# STM.net
KiCad netlist of a schematic drawn in Altium Designer
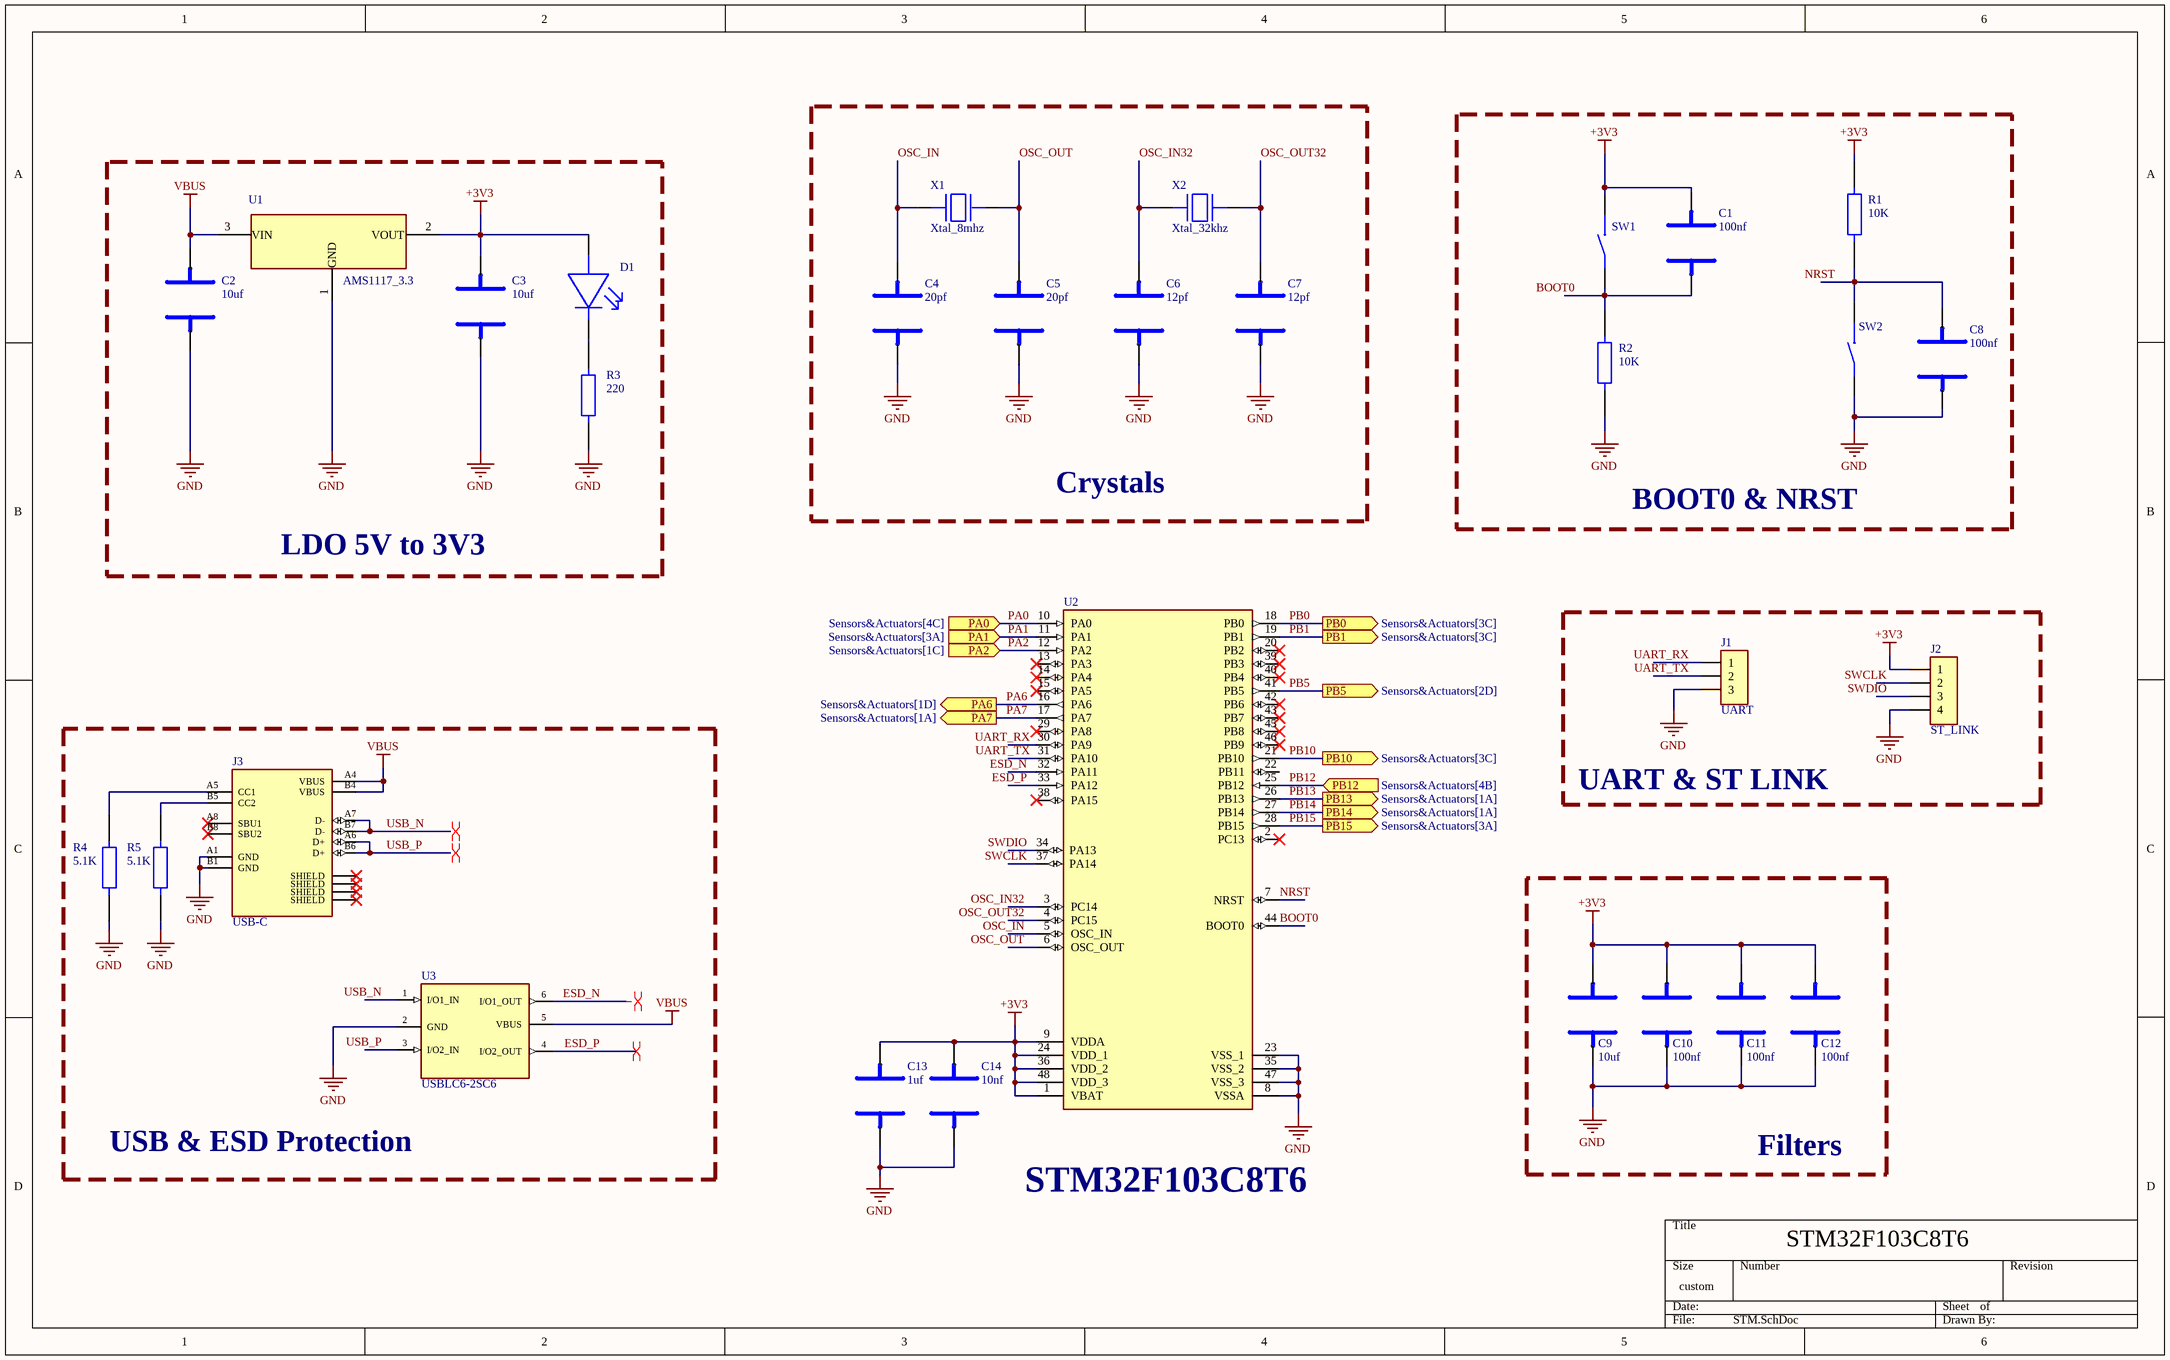
[diagram p0: STM.SchDoc]

(export (version "E")
  (design (tool "Eeschema 10.0.6"))
  (components
    (comp (ref "C1")
      (value "100nf")
      (footprint "Cap_0805")
      (description "CAP CER 100nF 50V X7R 0805")
      (fields (field (name "MFR") "Samsung Electro-Mechanics") (field (name "MFR PART#") "CL21B104KBCNNNC"))
      (libsource (lib "project") (part "Cap_0805_100nf"))
    )
    (comp (ref "C2")
      (value "10uf")
      (footprint "Cap_0805")
      (description "CAP CER 10uF 25V X5R 0805")
      (fields (field (name "MFR") "Samsung Electro-Mechanics") (field (name "MFR PART#") "CL21A106KAYNNNE"))
      (libsource (lib "project") (part "Cap_0805_10uf"))
    )
    (comp (ref "C3")
      (value "10uf")
      (footprint "Cap_0805")
      (description "CAP CER 10uF 25V X5R 0805")
      (fields (field (name "MFR") "Samsung Electro-Mechanics") (field (name "MFR PART#") "CL21A106KAYNNNE"))
      (libsource (lib "project") (part "Cap_0805_10uf"))
    )
    (comp (ref "C4")
      (value "20pf")
      (footprint "Cap_0805")
      (description "CAP CER 20pF 50V C0G 0805")
      (fields (field (name "MFR") "Samsung Electro-Mechanics") (field (name "MFR PART#") "CL21C200JBANNNC"))
      (libsource (lib "project") (part "Cap_0805_20pf"))
    )
    (comp (ref "C5")
      (value "20pf")
      (footprint "Cap_0805")
      (description "CAP CER 20pF 50V C0G 0805")
      (fields (field (name "MFR") "Samsung Electro-Mechanics") (field (name "MFR PART#") "CL21C200JBANNNC"))
      (libsource (lib "project") (part "Cap_0805_20pf"))
    )
    (comp (ref "C6")
      (value "12pf")
      (footprint "Cap_0805")
      (description "CAP CER 12pF 50V C0G 0805")
      (fields (field (name "MFR") "Samsung Electro-Mechanics") (field (name "MFR PART#") "CL21C120JBANNNC"))
      (libsource (lib "project") (part "Cap_0805_12pf"))
    )
    (comp (ref "C7")
      (value "12pf")
      (footprint "Cap_0805")
      (description "CAP CER 12pF 50V C0G 0805")
      (fields (field (name "MFR") "Samsung Electro-Mechanics") (field (name "MFR PART#") "CL21C120JBANNNC"))
      (libsource (lib "project") (part "Cap_0805_12pf"))
    )
    (comp (ref "C8")
      (value "100nf")
      (footprint "Cap_0805")
      (description "CAP CER 100nF 50V X7R 0805")
      (fields (field (name "MFR") "Samsung Electro-Mechanics") (field (name "MFR PART#") "CL21B104KBCNNNC"))
      (libsource (lib "project") (part "Cap_0805_100nf"))
    )
    (comp (ref "C9")
      (value "10uf")
      (footprint "Cap_0805")
      (description "CAP CER 10uF 25V X5R 0805")
      (fields (field (name "MFR") "Samsung Electro-Mechanics") (field (name "MFR PART#") "CL21A106KAYNNNE"))
      (libsource (lib "project") (part "Cap_0805_10uf"))
    )
    (comp (ref "C10")
      (value "100nf")
      (footprint "Cap_0805")
      (description "CAP CER 100nF 50V X7R 0805")
      (fields (field (name "MFR") "Samsung Electro-Mechanics") (field (name "MFR PART#") "CL21B104KBCNNNC"))
      (libsource (lib "project") (part "Cap_0805_100nf"))
    )
    (comp (ref "C11")
      (value "100nf")
      (footprint "Cap_0805")
      (description "CAP CER 100nF 50V X7R 0805")
      (fields (field (name "MFR") "Samsung Electro-Mechanics") (field (name "MFR PART#") "CL21B104KBCNNNC"))
      (libsource (lib "project") (part "Cap_0805_100nf"))
    )
    (comp (ref "C12")
      (value "100nf")
      (footprint "Cap_0805")
      (description "CAP CER 100nF 50V X7R 0805")
      (fields (field (name "MFR") "Samsung Electro-Mechanics") (field (name "MFR PART#") "CL21B104KBCNNNC"))
      (libsource (lib "project") (part "Cap_0805_100nf"))
    )
    (comp (ref "C13")
      (value "1uf")
      (footprint "Cap_0805")
      (description "CAP CER 1uF 50V X7R 0805")
      (fields (field (name "MFR") "Samsung Electro-Mechanics") (field (name "MFR PART#") "CL21B105KBFNNNE"))
      (libsource (lib "project") (part "Cap_0805_1uf"))
    )
    (comp (ref "C14")
      (value "10nf")
      (footprint "Cap_0805")
      (description "CAP CER 10nF 50V X7R 0805")
      (fields (field (name "MFR") "Samsung Electro-Mechanics") (field (name "MFR PART#") "CL21B103KBANNNC"))
      (libsource (lib "project") (part "Cap_0805_10nf"))
    )
    (comp (ref "D1")
      (value "LED_0805")
      (footprint "LED_0805")
      (description "LED RED 0805 SMD")
      (fields (field (name "MFR") "YONGYUTAI") (field (name "MFR PART#") "YLED0805R"))
      (libsource (lib "project") (part "LED_0805"))
    )
    (comp (ref "J1")
      (value "UART")
      (footprint "pin_header_3")
      (fields
        (field (name "MFR") "hanxia")
        (field (name "MFR PART#") "HX PH254-01-03-Z-L11.5 pcb pin header")
      )
      (libsource (lib "project") (part "pin_header_3"))
    )
    (comp (ref "J2")
      (value "ST_LINK")
      (footprint "pin_header_4")
      (fields
        (field (name "MFR") "hanxia")
        (field (name "MFR PART#") "HX PH254-01-04-Z-L11.5 straight pin header")
      )
      (libsource (lib "project") (part "pin_header_4"))
    )
    (comp (ref "J3")
      (value "USB-C")
      (footprint "USB_C")
      (description "CONN RCPT Type-C 16POS SMD")
      (fields (field (name "MFR") "Korean Hroparts Elec") (field (name "MFR PART#") "TYPE-C-31-M-12"))
      (libsource (lib "project") (part "USB-C"))
    )
    (comp (ref "R1")
      (value "10K")
      (footprint "RES_0805")
      (description "RES 10kΩ ±0.1% 125mW 0805")
      (fields (field (name "MFR") "YAGEO") (field (name "MFR PART#") "RT0805BRD0710KL"))
      (libsource (lib "project") (part "RES_0805_10K"))
    )
    (comp (ref "R2")
      (value "10K")
      (footprint "RES_0805")
      (description "RES 10kΩ ±0.1% 125mW 0805")
      (fields (field (name "MFR") "YAGEO") (field (name "MFR PART#") "RT0805BRD0710KL"))
      (libsource (lib "project") (part "RES_0805_10K"))
    )
    (comp (ref "R3")
      (value "220")
      (footprint "RES_0805")
      (description "RES 220Ω ±0.1% 125mW 0805")
      (fields (field (name "MFR") "YAGEO") (field (name "MFR PART#") "RT0805BRD07220RL"))
      (libsource (lib "project") (part "RES_0805_220"))
    )
    (comp (ref "R4")
      (value "5.1K")
      (footprint "RES_0805")
      (description "RES 5.1kΩ ±1% 125mW 0805")
      (fields (field (name "MFR") "YAGEO") (field (name "MFR PART#") "RC0805FR-075K1L"))
      (libsource (lib "project") (part "RES_0805_5.1K"))
    )
    (comp (ref "R5")
      (value "5.1K")
      (footprint "RES_0805")
      (description "RES 5.1kΩ ±1% 125mW 0805")
      (fields (field (name "MFR") "YAGEO") (field (name "MFR PART#") "RC0805FR-075K1L"))
      (libsource (lib "project") (part "RES_0805_5.1K"))
    )
    (comp (ref "SW1")
      (value "Switch")
      (footprint "switch")
      (description "SWITCH TACTILE SPST SMD")
      (fields (field (name "MFR") "SHOU HAN") (field (name "MFR PART#") "TS342A2P-WZ"))
      (libsource (lib "project") (part "Switch"))
    )
    (comp (ref "SW2")
      (value "Switch")
      (footprint "switch")
      (description "SWITCH TACTILE SPST SMD")
      (fields (field (name "MFR") "SHOU HAN") (field (name "MFR PART#") "TS342A2P-WZ"))
      (libsource (lib "project") (part "Switch"))
    )
    (comp (ref "U1")
      (value "AMS1117_3.3")
      (footprint "AMS1117")
      (description "1A Low Dropout (LDO) Regulator")
      (fields (field (name "MFR") "Advanced Monolithic Systems") (field (name "MFR PART#") "AMS1117-3.3"))
      (libsource (lib "project") (part "AMS1117_3.3"))
    )
    (comp (ref "U2")
      (value "STM32F103C8T6")
      (footprint "STM32F103C8T6")
      (fields (field (name "MFR") "ST"))
      (libsource (lib "project") (part "STM32F103C8T6"))
    )
    (comp (ref "U3")
      (value "USBLC6-2SC6")
      (footprint "USBLC6-2SC6")
      (description "ESD DIODE 5.25VWM 17VC SOT-23-6L")
      (fields (field (name "MFR") "ST"))
      (libsource (lib "project") (part "USBLC6-2SC6"))
    )
    (comp (ref "X1")
      (value "Xtal_8mhz")
      (footprint "Xtal_8mhz")
      (description "CRYSTAL 8MHz 20pF SMD")
      (fields (field (name "MFR") "YXC Crystal Oscillators") (field (name "MFR PART#") "X49SM8MSD2SC"))
      (libsource (lib "project") (part "Xtal_8mhz"))
    )
    (comp (ref "X2")
      (value "Xtal_32khz")
      (footprint "Xtal_32khz")
      (description "CRYSTAL 32.768kHz 12.5pF SMD")
      (fields (field (name "MFR") "NDK") (field (name "MFR PART#") "NX3215SA-32.768K-STD-MUA-8"))
      (libsource (lib "project") (part "Xtal_32khz"))
    )
  )
  (nets
    (net (code "1") (name "+3V3") (class "Default")
      (node (ref "C1") (pin "2") (pinfunction "2_2") (pintype "passive"))
      (node (ref "C10") (pin "2") (pinfunction "2_2") (pintype "passive"))
      (node (ref "C11") (pin "2") (pinfunction "2_2") (pintype "passive"))
      (node (ref "C12") (pin "2") (pinfunction "2_2") (pintype "passive"))
      (node (ref "C13") (pin "2") (pinfunction "2_2") (pintype "passive"))
      (node (ref "C14") (pin "2") (pinfunction "2_2") (pintype "passive"))
      (node (ref "C3") (pin "2") (pinfunction "2_2") (pintype "passive"))
      (node (ref "C9") (pin "2") (pinfunction "2_2") (pintype "passive"))
      (node (ref "D1") (pin "1") (pintype "passive"))
      (node (ref "J2") (pin "1") (pinfunction "1_1") (pintype "passive"))
      (node (ref "R1") (pin "1") (pinfunction "1_1") (pintype "passive"))
      (node (ref "SW1") (pin "2") (pinfunction "2_2") (pintype "passive"))
      (node (ref "U1") (pin "2") (pinfunction "VOUT_2") (pintype "passive"))
      (node (ref "U2") (pin "1") (pinfunction "VBAT_1") (pintype "power_in"))
      (node (ref "U2") (pin "24") (pinfunction "VDD_1_24") (pintype "power_in"))
      (node (ref "U2") (pin "36") (pinfunction "VDD_2_36") (pintype "power_in"))
      (node (ref "U2") (pin "48") (pinfunction "VDD_3_48") (pintype "power_in"))
      (node (ref "U2") (pin "9") (pinfunction "VDDA_9") (pintype "power_in"))
    )
    (net (code "2") (name "/BOOT0") (class "Default")
      (node (ref "C1") (pin "1") (pinfunction "1_1") (pintype "passive"))
      (node (ref "R2") (pin "2") (pinfunction "2_2") (pintype "passive"))
      (node (ref "SW1") (pin "1") (pinfunction "1_1") (pintype "passive"))
      (node (ref "U2") (pin "44") (pinfunction "BOOT0_44") (pintype "bidirectional"))
    )
    (net (code "3") (name "/ESD_N") (class "Default")
      (node (ref "U2") (pin "32") (pinfunction "PA11_32") (pintype "input"))
      (node (ref "U3") (pin "6") (pinfunction "I/O1_OUT_6") (pintype "output"))
    )
    (net (code "4") (name "/ESD_P") (class "Default")
      (node (ref "U2") (pin "33") (pinfunction "PA12_33") (pintype "input"))
      (node (ref "U3") (pin "4") (pinfunction "I/O2_OUT_4") (pintype "output"))
    )
    (net (code "5") (name "/NRST") (class "Default")
      (node (ref "C8") (pin "2") (pinfunction "2_2") (pintype "passive"))
      (node (ref "R1") (pin "2") (pinfunction "2_2") (pintype "passive"))
      (node (ref "SW2") (pin "2") (pinfunction "2_2") (pintype "passive"))
      (node (ref "U2") (pin "7") (pinfunction "NRST_7") (pintype "bidirectional"))
    )
    (net (code "6") (name "/OSC_IN") (class "Default")
      (node (ref "C4") (pin "2") (pinfunction "2_2") (pintype "passive"))
      (node (ref "U2") (pin "5") (pinfunction "OSC_IN_5") (pintype "bidirectional"))
      (node (ref "X1") (pin "1") (pinfunction "1_1") (pintype "passive"))
    )
    (net (code "7") (name "/OSC_IN32") (class "Default")
      (node (ref "C6") (pin "2") (pinfunction "2_2") (pintype "passive"))
      (node (ref "U2") (pin "3") (pinfunction "PC14_3") (pintype "bidirectional"))
      (node (ref "X2") (pin "1") (pinfunction "1_1") (pintype "passive"))
    )
    (net (code "8") (name "/OSC_OUT") (class "Default")
      (node (ref "C5") (pin "2") (pinfunction "2_2") (pintype "passive"))
      (node (ref "U2") (pin "6") (pinfunction "OSC_OUT_6") (pintype "bidirectional"))
      (node (ref "X1") (pin "2") (pinfunction "2_2") (pintype "passive"))
    )
    (net (code "9") (name "/OSC_OUT32") (class "Default")
      (node (ref "C7") (pin "2") (pinfunction "2_2") (pintype "passive"))
      (node (ref "U2") (pin "4") (pinfunction "PC15_4") (pintype "bidirectional"))
      (node (ref "X2") (pin "2") (pinfunction "2_2") (pintype "passive"))
    )
    (net (code "10") (name "/PA0") (class "Default")
      (node (ref "U2") (pin "10") (pinfunction "PA0_10") (pintype "input"))
    )
    (net (code "11") (name "/PA1") (class "Default")
      (node (ref "U2") (pin "11") (pinfunction "PA1_11") (pintype "input"))
    )
    (net (code "12") (name "/PA2") (class "Default")
      (node (ref "U2") (pin "12") (pinfunction "PA2_12") (pintype "input"))
    )
    (net (code "13") (name "/PA6") (class "Default")
      (node (ref "U2") (pin "16") (pinfunction "PA6_16") (pintype "output"))
    )
    (net (code "14") (name "/PA7") (class "Default")
      (node (ref "U2") (pin "17") (pinfunction "PA7_17") (pintype "output"))
    )
    (net (code "15") (name "/PB0") (class "Default")
      (node (ref "U2") (pin "18") (pinfunction "PB0_18") (pintype "output"))
    )
    (net (code "16") (name "/PB1") (class "Default")
      (node (ref "U2") (pin "19") (pinfunction "PB1_19") (pintype "output"))
    )
    (net (code "17") (name "/PB5") (class "Default")
      (node (ref "U2") (pin "41") (pinfunction "PB5_41") (pintype "output"))
    )
    (net (code "18") (name "/PB10") (class "Default")
      (node (ref "U2") (pin "21") (pinfunction "PB10_21") (pintype "output"))
    )
    (net (code "19") (name "/PB12") (class "Default")
      (node (ref "U2") (pin "25") (pinfunction "PB12_25") (pintype "input"))
    )
    (net (code "20") (name "/PB13") (class "Default")
      (node (ref "U2") (pin "26") (pinfunction "PB13_26") (pintype "output"))
    )
    (net (code "21") (name "/PB14") (class "Default")
      (node (ref "U2") (pin "27") (pinfunction "PB14_27") (pintype "output"))
    )
    (net (code "22") (name "/PB15") (class "Default")
      (node (ref "U2") (pin "28") (pinfunction "PB15_28") (pintype "output"))
    )
    (net (code "23") (name "/SWCLK") (class "Default")
      (node (ref "J2") (pin "2") (pinfunction "2_2") (pintype "passive"))
      (node (ref "U2") (pin "37") (pinfunction "PA14_37") (pintype "bidirectional"))
    )
    (net (code "24") (name "/SWDIO") (class "Default")
      (node (ref "J2") (pin "3") (pinfunction "3_3") (pintype "passive"))
      (node (ref "U2") (pin "34") (pinfunction "PA13_34") (pintype "bidirectional"))
    )
    (net (code "25") (name "/UART_RX") (class "Default")
      (node (ref "J1") (pin "1") (pinfunction "1_1") (pintype "passive"))
      (node (ref "U2") (pin "30") (pinfunction "PA9_30") (pintype "bidirectional"))
    )
    (net (code "26") (name "/UART_TX") (class "Default")
      (node (ref "J1") (pin "2") (pinfunction "2_2") (pintype "passive"))
      (node (ref "U2") (pin "31") (pinfunction "PA10_31") (pintype "bidirectional"))
    )
    (net (code "27") (name "/USB_N") (class "Default")
      (node (ref "J3") (pin "A7") (pinfunction "D-_A7") (pintype "bidirectional"))
      (node (ref "J3") (pin "B7") (pinfunction "D-_B7") (pintype "bidirectional"))
      (node (ref "U3") (pin "1") (pinfunction "I/O1_IN_1") (pintype "input"))
    )
    (net (code "28") (name "/USB_P") (class "Default")
      (node (ref "J3") (pin "A6") (pinfunction "D+_A6") (pintype "bidirectional"))
      (node (ref "J3") (pin "B6") (pinfunction "D+_B6") (pintype "bidirectional"))
      (node (ref "U3") (pin "3") (pinfunction "I/O2_IN_3") (pintype "input"))
    )
    (net (code "29") (name "GND") (class "Default")
      (node (ref "C10") (pin "1") (pinfunction "1_1") (pintype "passive"))
      (node (ref "C11") (pin "1") (pinfunction "1_1") (pintype "passive"))
      (node (ref "C12") (pin "1") (pinfunction "1_1") (pintype "passive"))
      (node (ref "C13") (pin "1") (pinfunction "1_1") (pintype "passive"))
      (node (ref "C14") (pin "1") (pinfunction "1_1") (pintype "passive"))
      (node (ref "C2") (pin "1") (pinfunction "1_1") (pintype "passive"))
      (node (ref "C3") (pin "1") (pinfunction "1_1") (pintype "passive"))
      (node (ref "C4") (pin "1") (pinfunction "1_1") (pintype "passive"))
      (node (ref "C5") (pin "1") (pinfunction "1_1") (pintype "passive"))
      (node (ref "C6") (pin "1") (pinfunction "1_1") (pintype "passive"))
      (node (ref "C7") (pin "1") (pinfunction "1_1") (pintype "passive"))
      (node (ref "C8") (pin "1") (pinfunction "1_1") (pintype "passive"))
      (node (ref "C9") (pin "1") (pinfunction "1_1") (pintype "passive"))
      (node (ref "J1") (pin "3") (pinfunction "3_3") (pintype "passive"))
      (node (ref "J2") (pin "4") (pinfunction "4_4") (pintype "passive"))
      (node (ref "J3") (pin "A1") (pinfunction "GND_A1") (pintype "power_in"))
      (node (ref "J3") (pin "B1") (pinfunction "GND_B1") (pintype "power_in"))
      (node (ref "R2") (pin "1") (pinfunction "1_1") (pintype "passive"))
      (node (ref "R3") (pin "2") (pinfunction "2_2") (pintype "passive"))
      (node (ref "R4") (pin "2") (pinfunction "2_2") (pintype "passive"))
      (node (ref "R5") (pin "2") (pinfunction "2_2") (pintype "passive"))
      (node (ref "SW2") (pin "1") (pinfunction "1_1") (pintype "passive"))
      (node (ref "U1") (pin "1") (pinfunction "GND_1") (pintype "passive"))
      (node (ref "U2") (pin "23") (pinfunction "VSS_1_23") (pintype "power_in"))
      (node (ref "U2") (pin "35") (pinfunction "VSS_2_35") (pintype "power_in"))
      (node (ref "U2") (pin "47") (pinfunction "VSS_3_47") (pintype "power_in"))
      (node (ref "U2") (pin "8") (pinfunction "VSSA_8") (pintype "power_in"))
      (node (ref "U3") (pin "2") (pinfunction "GND_2") (pintype "passive"))
    )
    (net (code "30") (name "Net-(D1-Pad2)") (class "Default")
      (node (ref "D1") (pin "2") (pintype "passive"))
      (node (ref "R3") (pin "1") (pinfunction "1_1") (pintype "passive"))
    )
    (net (code "31") (name "Net-(J3-CC1)") (class "Default")
      (node (ref "J3") (pin "A5") (pinfunction "CC1_A5") (pintype "passive"))
      (node (ref "R4") (pin "1") (pinfunction "1_1") (pintype "passive"))
    )
    (net (code "32") (name "Net-(J3-CC2)") (class "Default")
      (node (ref "J3") (pin "B5") (pinfunction "CC2_B5") (pintype "passive"))
      (node (ref "R5") (pin "1") (pinfunction "1_1") (pintype "passive"))
    )
    (net (code "33") (name "VBUS") (class "Default")
      (node (ref "C2") (pin "2") (pinfunction "2_2") (pintype "passive"))
      (node (ref "J3") (pin "A4") (pinfunction "VBUS_A4") (pintype "passive"))
      (node (ref "J3") (pin "B4") (pinfunction "VBUS_B4") (pintype "passive"))
      (node (ref "U1") (pin "3") (pinfunction "VIN_3") (pintype "passive"))
      (node (ref "U3") (pin "5") (pinfunction "VBUS_5") (pintype "passive"))
    )
    (net (code "34") (name "unconnected-(J3-SBU1-PadA8)") (class "Default")
      (node (ref "J3") (pin "A8") (pinfunction "SBU1_A8") (pintype "passive+no_connect"))
    )
    (net (code "35") (name "unconnected-(J3-SBU2-PadB8)") (class "Default")
      (node (ref "J3") (pin "B8") (pinfunction "SBU2_B8") (pintype "passive+no_connect"))
    )
    (net (code "36") (name "unconnected-(J3-SHIELD-PadS1)") (class "Default")
      (node (ref "J3") (pin "S1") (pinfunction "SHIELD_S1") (pintype "passive+no_connect"))
    )
    (net (code "37") (name "unconnected-(J3-SHIELD-PadS2)") (class "Default")
      (node (ref "J3") (pin "S2") (pinfunction "SHIELD_S2") (pintype "passive+no_connect"))
    )
    (net (code "38") (name "unconnected-(J3-SHIELD-PadS3)") (class "Default")
      (node (ref "J3") (pin "S3") (pinfunction "SHIELD_S3") (pintype "passive+no_connect"))
    )
    (net (code "39") (name "unconnected-(J3-SHIELD-PadS4)") (class "Default")
      (node (ref "J3") (pin "S4") (pinfunction "SHIELD_S4") (pintype "passive+no_connect"))
    )
    (net (code "40") (name "unconnected-(U2-PA3-Pad13)") (class "Default")
      (node (ref "U2") (pin "13") (pinfunction "PA3_13") (pintype "bidirectional+no_connect"))
    )
    (net (code "41") (name "unconnected-(U2-PA4-Pad14)") (class "Default")
      (node (ref "U2") (pin "14") (pinfunction "PA4_14") (pintype "bidirectional+no_connect"))
    )
    (net (code "42") (name "unconnected-(U2-PA5-Pad15)") (class "Default")
      (node (ref "U2") (pin "15") (pinfunction "PA5_15") (pintype "bidirectional+no_connect"))
    )
    (net (code "43") (name "unconnected-(U2-PA8-Pad29)") (class "Default")
      (node (ref "U2") (pin "29") (pinfunction "PA8_29") (pintype "bidirectional+no_connect"))
    )
    (net (code "44") (name "unconnected-(U2-PA15-Pad38)") (class "Default")
      (node (ref "U2") (pin "38") (pinfunction "PA15_38") (pintype "bidirectional+no_connect"))
    )
    (net (code "45") (name "unconnected-(U2-PB2-Pad20)") (class "Default")
      (node (ref "U2") (pin "20") (pinfunction "PB2_20") (pintype "bidirectional+no_connect"))
    )
    (net (code "46") (name "unconnected-(U2-PB3-Pad39)") (class "Default")
      (node (ref "U2") (pin "39") (pinfunction "PB3_39") (pintype "bidirectional+no_connect"))
    )
    (net (code "47") (name "unconnected-(U2-PB4-Pad40)") (class "Default")
      (node (ref "U2") (pin "40") (pinfunction "PB4_40") (pintype "bidirectional+no_connect"))
    )
    (net (code "48") (name "unconnected-(U2-PB6-Pad42)") (class "Default")
      (node (ref "U2") (pin "42") (pinfunction "PB6_42") (pintype "bidirectional+no_connect"))
    )
    (net (code "49") (name "unconnected-(U2-PB7-Pad43)") (class "Default")
      (node (ref "U2") (pin "43") (pinfunction "PB7_43") (pintype "bidirectional+no_connect"))
    )
    (net (code "50") (name "unconnected-(U2-PB8-Pad45)") (class "Default")
      (node (ref "U2") (pin "45") (pinfunction "PB8_45") (pintype "bidirectional+no_connect"))
    )
    (net (code "51") (name "unconnected-(U2-PB9-Pad46)") (class "Default")
      (node (ref "U2") (pin "46") (pinfunction "PB9_46") (pintype "bidirectional+no_connect"))
    )
    (net (code "52") (name "unconnected-(U2-PB11-Pad22)") (class "Default")
      (node (ref "U2") (pin "22") (pinfunction "PB11_22") (pintype "bidirectional"))
    )
    (net (code "53") (name "unconnected-(U2-PC13-Pad2)") (class "Default")
      (node (ref "U2") (pin "2") (pinfunction "PC13_2") (pintype "bidirectional+no_connect"))
    )
  )
)
